# TicTacToe.net
KiCad netlist of a schematic drawn in EAGLE
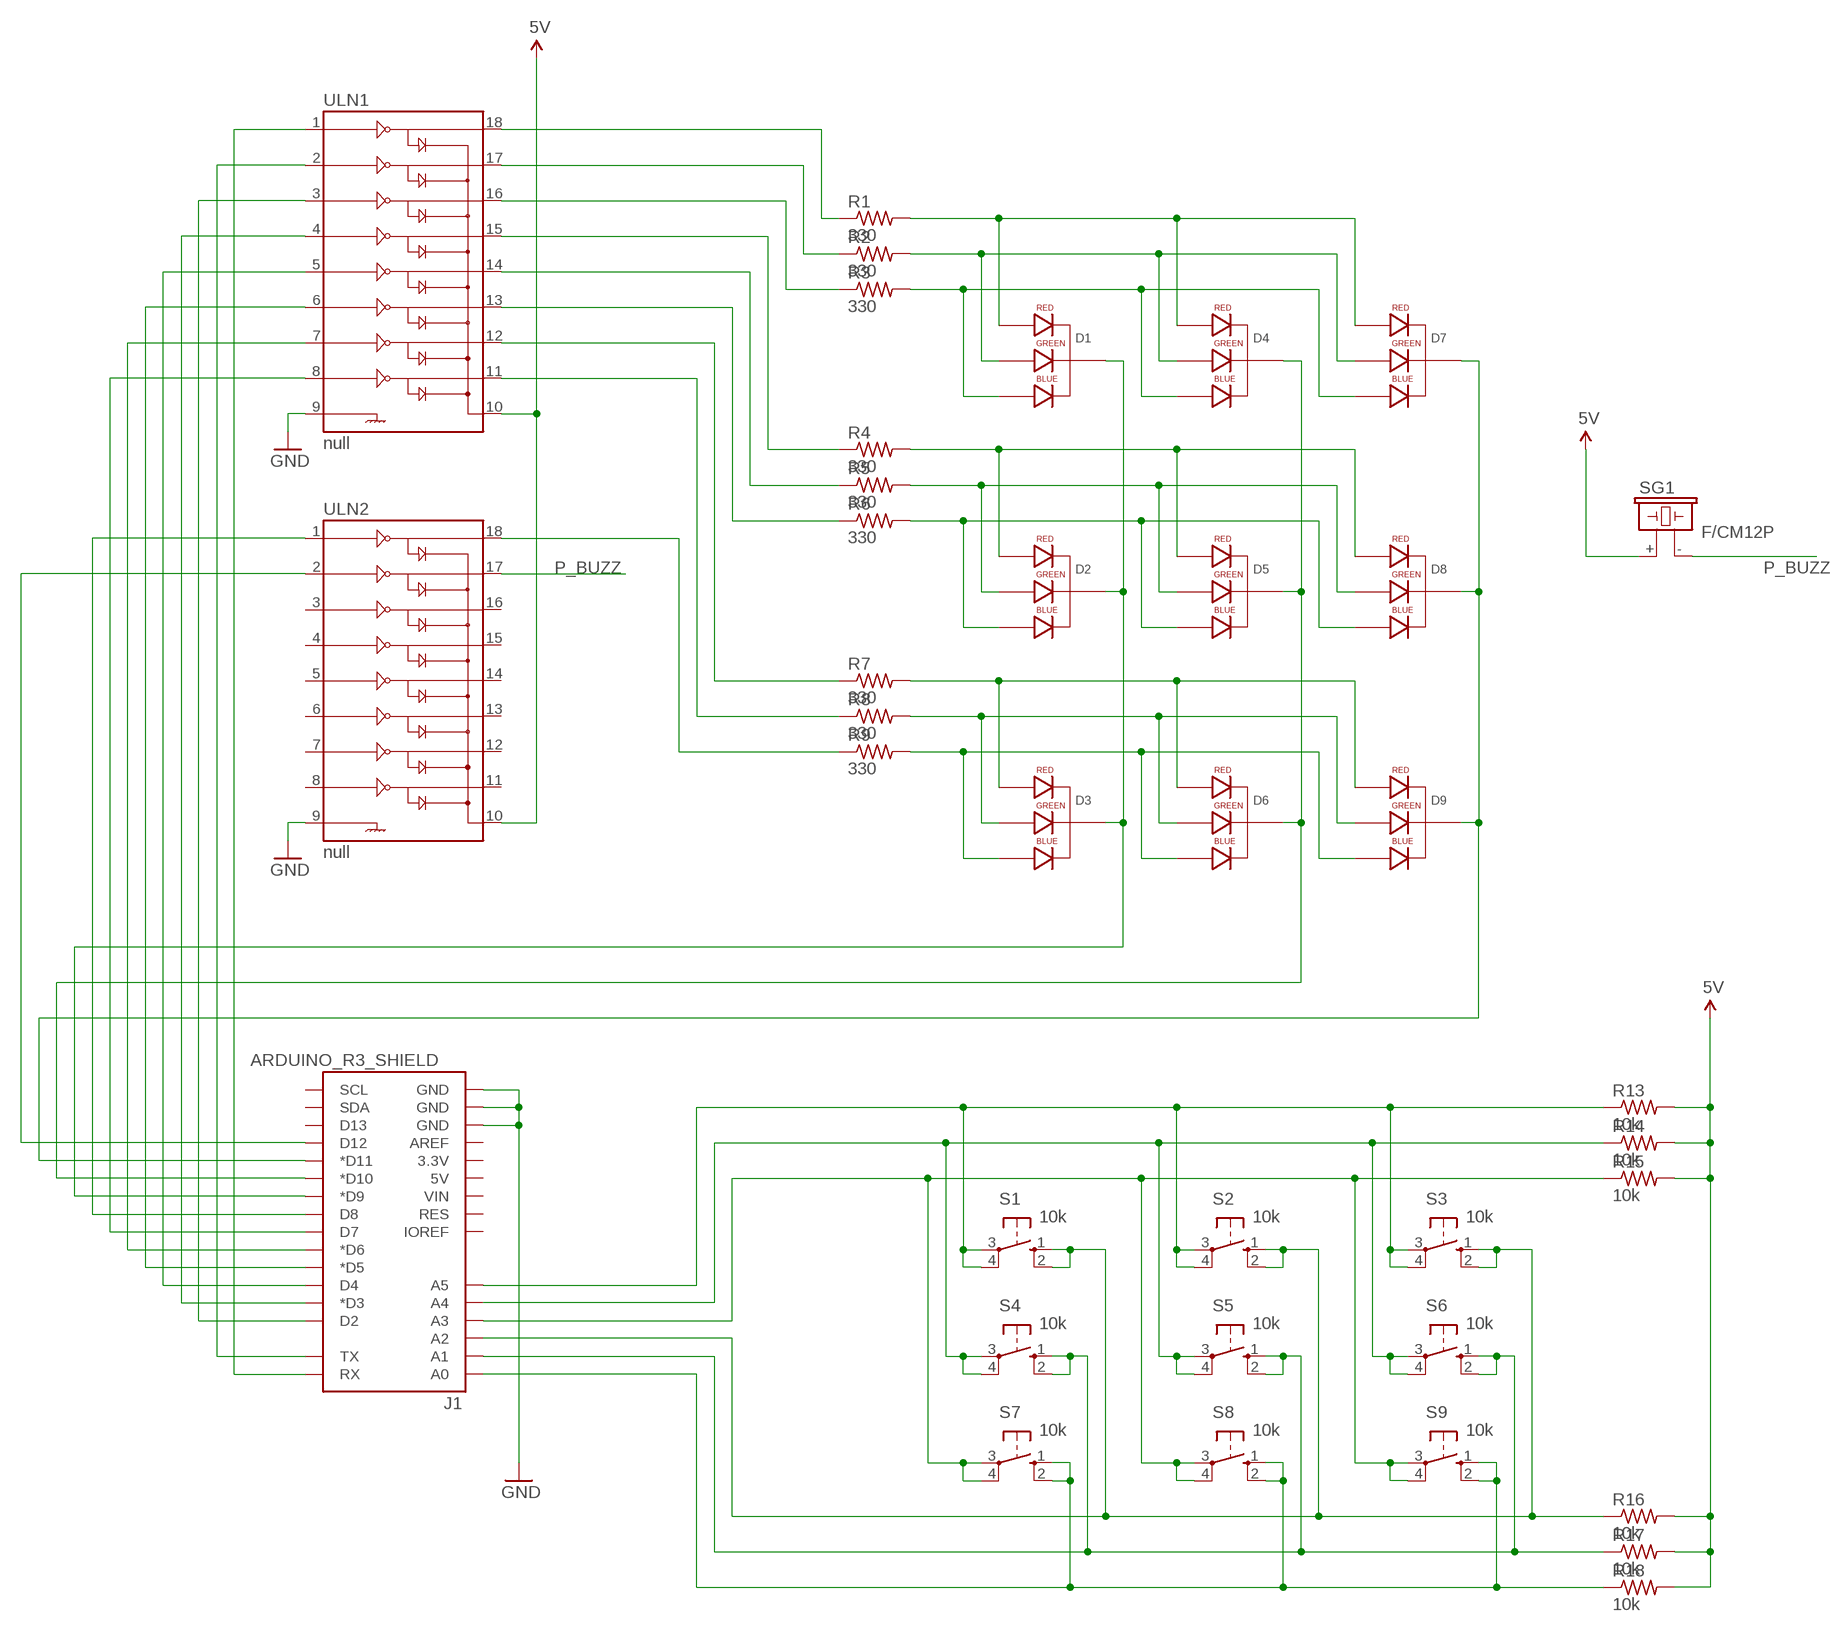
[diagram p0: schematic, sheet 1]

(export (version "E")
  (design (tool "Eeschema 10.0.6"))
  (components
    (comp (ref "D1")
      (value "LED-RGB-CC-THRUCLEAR")
      (footprint "eagle-import:LED-RGB-THRU")
      (libsource (lib "eagle-import") (part "LED-RGB-CC-THRUCLEAR"))
    )
    (comp (ref "D2")
      (value "LED-RGB-CC-THRUCLEAR")
      (footprint "eagle-import:LED-RGB-THRU")
      (libsource (lib "eagle-import") (part "LED-RGB-CC-THRUCLEAR"))
    )
    (comp (ref "D3")
      (value "LED-RGB-CC-THRUCLEAR")
      (footprint "eagle-import:LED-RGB-THRU")
      (libsource (lib "eagle-import") (part "LED-RGB-CC-THRUCLEAR"))
    )
    (comp (ref "D4")
      (value "LED-RGB-CC-THRUCLEAR")
      (footprint "eagle-import:LED-RGB-THRU")
      (libsource (lib "eagle-import") (part "LED-RGB-CC-THRUCLEAR"))
    )
    (comp (ref "D5")
      (value "LED-RGB-CC-THRUCLEAR")
      (footprint "eagle-import:LED-RGB-THRU")
      (libsource (lib "eagle-import") (part "LED-RGB-CC-THRUCLEAR"))
    )
    (comp (ref "D6")
      (value "LED-RGB-CC-THRUCLEAR")
      (footprint "eagle-import:LED-RGB-THRU")
      (libsource (lib "eagle-import") (part "LED-RGB-CC-THRUCLEAR"))
    )
    (comp (ref "D7")
      (value "LED-RGB-CC-THRUCLEAR")
      (footprint "eagle-import:LED-RGB-THRU")
      (libsource (lib "eagle-import") (part "LED-RGB-CC-THRUCLEAR"))
    )
    (comp (ref "D8")
      (value "LED-RGB-CC-THRUCLEAR")
      (footprint "eagle-import:LED-RGB-THRU")
      (libsource (lib "eagle-import") (part "LED-RGB-CC-THRUCLEAR"))
    )
    (comp (ref "D9")
      (value "LED-RGB-CC-THRUCLEAR")
      (footprint "eagle-import:LED-RGB-THRU")
      (libsource (lib "eagle-import") (part "LED-RGB-CC-THRUCLEAR"))
    )
    (comp (ref "J1")
      (value "ARDUINO_R3_SHIELD")
      (footprint "eagle-import:UNO_R3_SHIELD")
      (libsource (lib "eagle-import") (part "ARDUINO_R3_SHIELD"))
    )
    (comp (ref "R1")
      (value "330")
      (footprint "eagle-import:0204_7")
      (libsource (lib "eagle-import") (part "R-US_0204/7"))
    )
    (comp (ref "R2")
      (value "330")
      (footprint "eagle-import:0204_7")
      (libsource (lib "eagle-import") (part "R-US_0204/7"))
    )
    (comp (ref "R3")
      (value "330")
      (footprint "eagle-import:0204_7")
      (libsource (lib "eagle-import") (part "R-US_0204/7"))
    )
    (comp (ref "R4")
      (value "330")
      (footprint "eagle-import:0204_7")
      (libsource (lib "eagle-import") (part "R-US_0204/7"))
    )
    (comp (ref "R5")
      (value "330")
      (footprint "eagle-import:0204_7")
      (libsource (lib "eagle-import") (part "R-US_0204/7"))
    )
    (comp (ref "R6")
      (value "330")
      (footprint "eagle-import:0204_7")
      (libsource (lib "eagle-import") (part "R-US_0204/7"))
    )
    (comp (ref "R7")
      (value "330")
      (footprint "eagle-import:0204_7")
      (libsource (lib "eagle-import") (part "R-US_0204/7"))
    )
    (comp (ref "R8")
      (value "330")
      (footprint "eagle-import:0204_7")
      (libsource (lib "eagle-import") (part "R-US_0204/7"))
    )
    (comp (ref "R9")
      (value "330")
      (footprint "eagle-import:0204_7")
      (libsource (lib "eagle-import") (part "R-US_0204/7"))
    )
    (comp (ref "R13")
      (value "10k")
      (footprint "eagle-import:0204_7")
      (libsource (lib "eagle-import") (part "R-US_0204/7"))
    )
    (comp (ref "R14")
      (value "10k")
      (footprint "eagle-import:0204_7")
      (libsource (lib "eagle-import") (part "R-US_0204/7"))
    )
    (comp (ref "R15")
      (value "10k")
      (footprint "eagle-import:0204_7")
      (libsource (lib "eagle-import") (part "R-US_0204/7"))
    )
    (comp (ref "R16")
      (value "10k")
      (footprint "eagle-import:0204_7")
      (libsource (lib "eagle-import") (part "R-US_0204/7"))
    )
    (comp (ref "R17")
      (value "10k")
      (footprint "eagle-import:0204_7")
      (libsource (lib "eagle-import") (part "R-US_0204/7"))
    )
    (comp (ref "R18")
      (value "10k")
      (footprint "eagle-import:0204_7")
      (libsource (lib "eagle-import") (part "R-US_0204/7"))
    )
    (comp (ref "S1")
      (value "10k")
      (footprint "eagle-import:B3F-10XX")
      (fields (field (name "MPN") "B3F-1000"))
      (libsource (lib "eagle-import") (part "10-XX"))
    )
    (comp (ref "S2")
      (value "10k")
      (footprint "eagle-import:B3F-10XX")
      (fields (field (name "MPN") "B3F-1000"))
      (libsource (lib "eagle-import") (part "10-XX"))
    )
    (comp (ref "S3")
      (value "10k")
      (footprint "eagle-import:B3F-10XX")
      (fields (field (name "MPN") "B3F-1000"))
      (libsource (lib "eagle-import") (part "10-XX"))
    )
    (comp (ref "S4")
      (value "10k")
      (footprint "eagle-import:B3F-10XX")
      (fields (field (name "MPN") "B3F-1000"))
      (libsource (lib "eagle-import") (part "10-XX"))
    )
    (comp (ref "S5")
      (value "10k")
      (footprint "eagle-import:B3F-10XX")
      (fields (field (name "MPN") "B3F-1000"))
      (libsource (lib "eagle-import") (part "10-XX"))
    )
    (comp (ref "S6")
      (value "10k")
      (footprint "eagle-import:B3F-10XX")
      (fields (field (name "MPN") "B3F-1000"))
      (libsource (lib "eagle-import") (part "10-XX"))
    )
    (comp (ref "S7")
      (value "10k")
      (footprint "eagle-import:B3F-10XX")
      (fields (field (name "MPN") "B3F-1000"))
      (libsource (lib "eagle-import") (part "10-XX"))
    )
    (comp (ref "S8")
      (value "10k")
      (footprint "eagle-import:B3F-10XX")
      (fields (field (name "MPN") "B3F-1000"))
      (libsource (lib "eagle-import") (part "10-XX"))
    )
    (comp (ref "S9")
      (value "10k")
      (footprint "eagle-import:B3F-10XX")
      (fields (field (name "MPN") "B3F-1000"))
      (libsource (lib "eagle-import") (part "10-XX"))
    )
    (comp (ref "SG1")
      (value "F/CM12P")
      (footprint "eagle-import:F_CM12P")
      (libsource (lib "eagle-import") (part "F/CM12P"))
    )
    (comp (ref "ULN1")
      (value "null")
      (footprint "eagle-import:DIL18")
      (libsource (lib "eagle-import") (part "ULN2803DIP"))
    )
    (comp (ref "ULN2")
      (value "null")
      (footprint "eagle-import:DIL18")
      (libsource (lib "eagle-import") (part "ULN2803DIP"))
    )
  )
  (nets
    (net (code "1") (name "/P_BUZZ") (class "Default")
      (node (ref "SG1") (pin "-") (pinfunction "2_-") (pintype "passive"))
      (node (ref "ULN2") (pin "17") (pinfunction "17_17") (pintype "bidirectional"))
    )
    (net (code "2") (name "5V") (class "Default")
      (node (ref "R13") (pin "2") (pinfunction "2_2") (pintype "passive"))
      (node (ref "R14") (pin "2") (pinfunction "2_2") (pintype "passive"))
      (node (ref "R15") (pin "2") (pinfunction "2_2") (pintype "passive"))
      (node (ref "R16") (pin "2") (pinfunction "2_2") (pintype "passive"))
      (node (ref "R17") (pin "2") (pinfunction "2_2") (pintype "passive"))
      (node (ref "R18") (pin "2") (pinfunction "2_2") (pintype "passive"))
      (node (ref "SG1") (pin "+") (pinfunction "1_+") (pintype "passive"))
      (node (ref "ULN1") (pin "10") (pinfunction "10_10") (pintype "bidirectional"))
      (node (ref "ULN2") (pin "10") (pinfunction "10_10") (pintype "bidirectional"))
    )
    (net (code "3") (name "GND") (class "Default")
      (node (ref "J1") (pin "GND@0") (pinfunction "GND_GND@0") (pintype "bidirectional"))
      (node (ref "J1") (pin "GND@1") (pinfunction "GND_GND@1") (pintype "bidirectional"))
      (node (ref "J1") (pin "GND@2") (pinfunction "GND_GND@2") (pintype "bidirectional"))
      (node (ref "ULN1") (pin "9") (pinfunction "9_9") (pintype "bidirectional"))
      (node (ref "ULN2") (pin "9") (pinfunction "9_9") (pintype "bidirectional"))
    )
    (net (code "4") (name "Net-(D1-BLUE_CATHODE)") (class "Default")
      (node (ref "D1") (pin "4") (pinfunction "BLUE_CATHODE_4") (pintype "bidirectional"))
      (node (ref "D4") (pin "4") (pinfunction "BLUE_CATHODE_4") (pintype "bidirectional"))
      (node (ref "D7") (pin "4") (pinfunction "BLUE_CATHODE_4") (pintype "bidirectional"))
      (node (ref "R3") (pin "2") (pinfunction "2_2") (pintype "passive"))
    )
    (net (code "5") (name "Net-(D1-CATHODE)") (class "Default")
      (node (ref "D1") (pin "2") (pinfunction "CATHODE_2") (pintype "bidirectional"))
      (node (ref "D2") (pin "2") (pinfunction "CATHODE_2") (pintype "bidirectional"))
      (node (ref "D3") (pin "2") (pinfunction "CATHODE_2") (pintype "bidirectional"))
      (node (ref "J1") (pin "D9") (pinfunction "*D9_D9") (pintype "bidirectional"))
    )
    (net (code "6") (name "Net-(D1-GREEN_CATHODE)") (class "Default")
      (node (ref "D1") (pin "3") (pinfunction "GREEN_CATHODE_3") (pintype "bidirectional"))
      (node (ref "D4") (pin "3") (pinfunction "GREEN_CATHODE_3") (pintype "bidirectional"))
      (node (ref "D7") (pin "3") (pinfunction "GREEN_CATHODE_3") (pintype "bidirectional"))
      (node (ref "R2") (pin "2") (pinfunction "2_2") (pintype "passive"))
    )
    (net (code "7") (name "Net-(D1-RED_CATHODE)") (class "Default")
      (node (ref "D1") (pin "1") (pinfunction "RED_CATHODE_1") (pintype "bidirectional"))
      (node (ref "D4") (pin "1") (pinfunction "RED_CATHODE_1") (pintype "bidirectional"))
      (node (ref "D7") (pin "1") (pinfunction "RED_CATHODE_1") (pintype "bidirectional"))
      (node (ref "R1") (pin "2") (pinfunction "2_2") (pintype "passive"))
    )
    (net (code "8") (name "Net-(D2-BLUE_CATHODE)") (class "Default")
      (node (ref "D2") (pin "4") (pinfunction "BLUE_CATHODE_4") (pintype "bidirectional"))
      (node (ref "D5") (pin "4") (pinfunction "BLUE_CATHODE_4") (pintype "bidirectional"))
      (node (ref "D8") (pin "4") (pinfunction "BLUE_CATHODE_4") (pintype "bidirectional"))
      (node (ref "R6") (pin "2") (pinfunction "2_2") (pintype "passive"))
    )
    (net (code "9") (name "Net-(D2-GREEN_CATHODE)") (class "Default")
      (node (ref "D2") (pin "3") (pinfunction "GREEN_CATHODE_3") (pintype "bidirectional"))
      (node (ref "D5") (pin "3") (pinfunction "GREEN_CATHODE_3") (pintype "bidirectional"))
      (node (ref "D8") (pin "3") (pinfunction "GREEN_CATHODE_3") (pintype "bidirectional"))
      (node (ref "R5") (pin "2") (pinfunction "2_2") (pintype "passive"))
    )
    (net (code "10") (name "Net-(D2-RED_CATHODE)") (class "Default")
      (node (ref "D2") (pin "1") (pinfunction "RED_CATHODE_1") (pintype "bidirectional"))
      (node (ref "D5") (pin "1") (pinfunction "RED_CATHODE_1") (pintype "bidirectional"))
      (node (ref "D8") (pin "1") (pinfunction "RED_CATHODE_1") (pintype "bidirectional"))
      (node (ref "R4") (pin "2") (pinfunction "2_2") (pintype "passive"))
    )
    (net (code "11") (name "Net-(D3-BLUE_CATHODE)") (class "Default")
      (node (ref "D3") (pin "4") (pinfunction "BLUE_CATHODE_4") (pintype "bidirectional"))
      (node (ref "D6") (pin "4") (pinfunction "BLUE_CATHODE_4") (pintype "bidirectional"))
      (node (ref "D9") (pin "4") (pinfunction "BLUE_CATHODE_4") (pintype "bidirectional"))
      (node (ref "R9") (pin "2") (pinfunction "2_2") (pintype "passive"))
    )
    (net (code "12") (name "Net-(D3-GREEN_CATHODE)") (class "Default")
      (node (ref "D3") (pin "3") (pinfunction "GREEN_CATHODE_3") (pintype "bidirectional"))
      (node (ref "D6") (pin "3") (pinfunction "GREEN_CATHODE_3") (pintype "bidirectional"))
      (node (ref "D9") (pin "3") (pinfunction "GREEN_CATHODE_3") (pintype "bidirectional"))
      (node (ref "R8") (pin "2") (pinfunction "2_2") (pintype "passive"))
    )
    (net (code "13") (name "Net-(D3-RED_CATHODE)") (class "Default")
      (node (ref "D3") (pin "1") (pinfunction "RED_CATHODE_1") (pintype "bidirectional"))
      (node (ref "D6") (pin "1") (pinfunction "RED_CATHODE_1") (pintype "bidirectional"))
      (node (ref "D9") (pin "1") (pinfunction "RED_CATHODE_1") (pintype "bidirectional"))
      (node (ref "R7") (pin "2") (pinfunction "2_2") (pintype "passive"))
    )
    (net (code "14") (name "Net-(D4-CATHODE)") (class "Default")
      (node (ref "D4") (pin "2") (pinfunction "CATHODE_2") (pintype "bidirectional"))
      (node (ref "D5") (pin "2") (pinfunction "CATHODE_2") (pintype "bidirectional"))
      (node (ref "D6") (pin "2") (pinfunction "CATHODE_2") (pintype "bidirectional"))
      (node (ref "J1") (pin "D10") (pinfunction "*D10_D10") (pintype "bidirectional"))
    )
    (net (code "15") (name "Net-(D7-CATHODE)") (class "Default")
      (node (ref "D7") (pin "2") (pinfunction "CATHODE_2") (pintype "bidirectional"))
      (node (ref "D8") (pin "2") (pinfunction "CATHODE_2") (pintype "bidirectional"))
      (node (ref "D9") (pin "2") (pinfunction "CATHODE_2") (pintype "bidirectional"))
      (node (ref "J1") (pin "D11") (pinfunction "*D11_D11") (pintype "bidirectional"))
    )
    (net (code "16") (name "Net-(J1-*D3)") (class "Default")
      (node (ref "J1") (pin "D3") (pinfunction "*D3_D3") (pintype "bidirectional"))
      (node (ref "ULN1") (pin "4") (pinfunction "4_4") (pintype "bidirectional"))
    )
    (net (code "17") (name "Net-(J1-*D5)") (class "Default")
      (node (ref "J1") (pin "D5") (pinfunction "*D5_D5") (pintype "bidirectional"))
      (node (ref "ULN1") (pin "6") (pinfunction "6_6") (pintype "bidirectional"))
    )
    (net (code "18") (name "Net-(J1-*D6)") (class "Default")
      (node (ref "J1") (pin "D6") (pinfunction "*D6_D6") (pintype "bidirectional"))
      (node (ref "ULN1") (pin "7") (pinfunction "7_7") (pintype "bidirectional"))
    )
    (net (code "19") (name "Net-(J1-PadD2)") (class "Default")
      (node (ref "J1") (pin "D2") (pinfunction "D2_D2") (pintype "bidirectional"))
      (node (ref "ULN1") (pin "3") (pinfunction "3_3") (pintype "bidirectional"))
    )
    (net (code "20") (name "Net-(J1-PadD4)") (class "Default")
      (node (ref "J1") (pin "D4") (pinfunction "D4_D4") (pintype "bidirectional"))
      (node (ref "ULN1") (pin "5") (pinfunction "5_5") (pintype "bidirectional"))
    )
    (net (code "21") (name "Net-(J1-PadD7)") (class "Default")
      (node (ref "J1") (pin "D7") (pinfunction "D7_D7") (pintype "bidirectional"))
      (node (ref "ULN1") (pin "8") (pinfunction "8_8") (pintype "bidirectional"))
    )
    (net (code "22") (name "Net-(J1-PadD8)") (class "Default")
      (node (ref "J1") (pin "D8") (pinfunction "D8_D8") (pintype "bidirectional"))
      (node (ref "ULN2") (pin "1") (pinfunction "1_1") (pintype "bidirectional"))
    )
    (net (code "23") (name "Net-(J1-PadD12)") (class "Default")
      (node (ref "J1") (pin "D12") (pinfunction "D12_D12") (pintype "bidirectional"))
      (node (ref "ULN2") (pin "2") (pinfunction "2_2") (pintype "bidirectional"))
    )
    (net (code "24") (name "Net-(J1-PadRX)") (class "Default")
      (node (ref "J1") (pin "RX") (pinfunction "RX_RX") (pintype "bidirectional"))
      (node (ref "ULN1") (pin "1") (pinfunction "1_1") (pintype "bidirectional"))
    )
    (net (code "25") (name "Net-(J1-PadTX)") (class "Default")
      (node (ref "J1") (pin "TX") (pinfunction "TX_TX") (pintype "bidirectional"))
      (node (ref "ULN1") (pin "2") (pinfunction "2_2") (pintype "bidirectional"))
    )
    (net (code "26") (name "Net-(R1-Pad1)") (class "Default")
      (node (ref "R1") (pin "1") (pinfunction "1_1") (pintype "passive"))
      (node (ref "ULN1") (pin "18") (pinfunction "18_18") (pintype "bidirectional"))
    )
    (net (code "27") (name "Net-(R2-Pad1)") (class "Default")
      (node (ref "R2") (pin "1") (pinfunction "1_1") (pintype "passive"))
      (node (ref "ULN1") (pin "17") (pinfunction "17_17") (pintype "bidirectional"))
    )
    (net (code "28") (name "Net-(R3-Pad1)") (class "Default")
      (node (ref "R3") (pin "1") (pinfunction "1_1") (pintype "passive"))
      (node (ref "ULN1") (pin "16") (pinfunction "16_16") (pintype "bidirectional"))
    )
    (net (code "29") (name "Net-(R4-Pad1)") (class "Default")
      (node (ref "R4") (pin "1") (pinfunction "1_1") (pintype "passive"))
      (node (ref "ULN1") (pin "15") (pinfunction "15_15") (pintype "bidirectional"))
    )
    (net (code "30") (name "Net-(R5-Pad1)") (class "Default")
      (node (ref "R5") (pin "1") (pinfunction "1_1") (pintype "passive"))
      (node (ref "ULN1") (pin "14") (pinfunction "14_14") (pintype "bidirectional"))
    )
    (net (code "31") (name "Net-(R6-Pad1)") (class "Default")
      (node (ref "R6") (pin "1") (pinfunction "1_1") (pintype "passive"))
      (node (ref "ULN1") (pin "13") (pinfunction "13_13") (pintype "bidirectional"))
    )
    (net (code "32") (name "Net-(R7-Pad1)") (class "Default")
      (node (ref "R7") (pin "1") (pinfunction "1_1") (pintype "passive"))
      (node (ref "ULN1") (pin "12") (pinfunction "12_12") (pintype "bidirectional"))
    )
    (net (code "33") (name "Net-(R8-Pad1)") (class "Default")
      (node (ref "R8") (pin "1") (pinfunction "1_1") (pintype "passive"))
      (node (ref "ULN1") (pin "11") (pinfunction "11_11") (pintype "bidirectional"))
    )
    (net (code "34") (name "Net-(R9-Pad1)") (class "Default")
      (node (ref "R9") (pin "1") (pinfunction "1_1") (pintype "passive"))
      (node (ref "ULN2") (pin "18") (pinfunction "18_18") (pintype "bidirectional"))
    )
    (net (code "35") (name "Net-(S1-P)") (class "Default")
      (node (ref "J1") (pin "A5") (pinfunction "A5_A5") (pintype "bidirectional"))
      (node (ref "R13") (pin "1") (pinfunction "1_1") (pintype "passive"))
      (node (ref "S1") (pin "3") (pinfunction "P_3") (pintype "passive"))
      (node (ref "S1") (pin "4") (pinfunction "P1_4") (pintype "passive"))
      (node (ref "S2") (pin "3") (pinfunction "P_3") (pintype "passive"))
      (node (ref "S2") (pin "4") (pinfunction "P1_4") (pintype "passive"))
      (node (ref "S3") (pin "3") (pinfunction "P_3") (pintype "passive"))
      (node (ref "S3") (pin "4") (pinfunction "P1_4") (pintype "passive"))
    )
    (net (code "36") (name "Net-(S1-S)") (class "Default")
      (node (ref "J1") (pin "A2") (pinfunction "A2_A2") (pintype "bidirectional"))
      (node (ref "R16") (pin "1") (pinfunction "1_1") (pintype "passive"))
      (node (ref "S1") (pin "1") (pinfunction "S_1") (pintype "passive"))
      (node (ref "S1") (pin "2") (pinfunction "S1_2") (pintype "passive"))
      (node (ref "S2") (pin "1") (pinfunction "S_1") (pintype "passive"))
      (node (ref "S2") (pin "2") (pinfunction "S1_2") (pintype "passive"))
      (node (ref "S3") (pin "1") (pinfunction "S_1") (pintype "passive"))
      (node (ref "S3") (pin "2") (pinfunction "S1_2") (pintype "passive"))
    )
    (net (code "37") (name "Net-(S4-P)") (class "Default")
      (node (ref "J1") (pin "A4") (pinfunction "A4_A4") (pintype "bidirectional"))
      (node (ref "R14") (pin "1") (pinfunction "1_1") (pintype "passive"))
      (node (ref "S4") (pin "3") (pinfunction "P_3") (pintype "passive"))
      (node (ref "S4") (pin "4") (pinfunction "P1_4") (pintype "passive"))
      (node (ref "S5") (pin "3") (pinfunction "P_3") (pintype "passive"))
      (node (ref "S5") (pin "4") (pinfunction "P1_4") (pintype "passive"))
      (node (ref "S6") (pin "3") (pinfunction "P_3") (pintype "passive"))
      (node (ref "S6") (pin "4") (pinfunction "P1_4") (pintype "passive"))
    )
    (net (code "38") (name "Net-(S4-S)") (class "Default")
      (node (ref "J1") (pin "A1") (pinfunction "A1_A1") (pintype "bidirectional"))
      (node (ref "R17") (pin "1") (pinfunction "1_1") (pintype "passive"))
      (node (ref "S4") (pin "1") (pinfunction "S_1") (pintype "passive"))
      (node (ref "S4") (pin "2") (pinfunction "S1_2") (pintype "passive"))
      (node (ref "S5") (pin "1") (pinfunction "S_1") (pintype "passive"))
      (node (ref "S5") (pin "2") (pinfunction "S1_2") (pintype "passive"))
      (node (ref "S6") (pin "1") (pinfunction "S_1") (pintype "passive"))
      (node (ref "S6") (pin "2") (pinfunction "S1_2") (pintype "passive"))
    )
    (net (code "39") (name "Net-(S7-P)") (class "Default")
      (node (ref "J1") (pin "A3") (pinfunction "A3_A3") (pintype "bidirectional"))
      (node (ref "R15") (pin "1") (pinfunction "1_1") (pintype "passive"))
      (node (ref "S7") (pin "3") (pinfunction "P_3") (pintype "passive"))
      (node (ref "S7") (pin "4") (pinfunction "P1_4") (pintype "passive"))
      (node (ref "S8") (pin "3") (pinfunction "P_3") (pintype "passive"))
      (node (ref "S8") (pin "4") (pinfunction "P1_4") (pintype "passive"))
      (node (ref "S9") (pin "3") (pinfunction "P_3") (pintype "passive"))
      (node (ref "S9") (pin "4") (pinfunction "P1_4") (pintype "passive"))
    )
    (net (code "40") (name "Net-(S7-S)") (class "Default")
      (node (ref "J1") (pin "A0") (pinfunction "A0_A0") (pintype "bidirectional"))
      (node (ref "R18") (pin "1") (pinfunction "1_1") (pintype "passive"))
      (node (ref "S7") (pin "1") (pinfunction "S_1") (pintype "passive"))
      (node (ref "S7") (pin "2") (pinfunction "S1_2") (pintype "passive"))
      (node (ref "S8") (pin "1") (pinfunction "S_1") (pintype "passive"))
      (node (ref "S8") (pin "2") (pinfunction "S1_2") (pintype "passive"))
      (node (ref "S9") (pin "1") (pinfunction "S_1") (pintype "passive"))
      (node (ref "S9") (pin "2") (pinfunction "S1_2") (pintype "passive"))
    )
    (net (code "41") (name "unconnected-(J1-Pad3.3V)") (class "Default")
      (node (ref "J1") (pin "3.3V") (pinfunction "3.3V_3.3V") (pintype "bidirectional"))
    )
    (net (code "42") (name "unconnected-(J1-Pad5V)") (class "Default")
      (node (ref "J1") (pin "5V") (pinfunction "5V_5V") (pintype "bidirectional"))
    )
    (net (code "43") (name "unconnected-(J1-PadAREF)") (class "Default")
      (node (ref "J1") (pin "AREF") (pinfunction "AREF_AREF") (pintype "bidirectional"))
    )
    (net (code "44") (name "unconnected-(J1-PadD13)") (class "Default")
      (node (ref "J1") (pin "D13") (pinfunction "D13_D13") (pintype "bidirectional"))
    )
    (net (code "45") (name "unconnected-(J1-PadIOREF)") (class "Default")
      (node (ref "J1") (pin "IOREF") (pinfunction "IOREF_IOREF") (pintype "bidirectional"))
    )
    (net (code "46") (name "unconnected-(J1-PadRES)") (class "Default")
      (node (ref "J1") (pin "RES") (pinfunction "RES_RES") (pintype "bidirectional"))
    )
    (net (code "47") (name "unconnected-(J1-PadSCL)") (class "Default")
      (node (ref "J1") (pin "SCL") (pinfunction "SCL_SCL") (pintype "bidirectional"))
    )
    (net (code "48") (name "unconnected-(J1-PadSDA)") (class "Default")
      (node (ref "J1") (pin "SDA") (pinfunction "SDA_SDA") (pintype "bidirectional"))
    )
    (net (code "49") (name "unconnected-(J1-PadVIN)") (class "Default")
      (node (ref "J1") (pin "VIN") (pinfunction "VIN_VIN") (pintype "bidirectional"))
    )
    (net (code "50") (name "unconnected-(ULN2-Pad3)") (class "Default")
      (node (ref "ULN2") (pin "3") (pinfunction "3_3") (pintype "bidirectional"))
    )
    (net (code "51") (name "unconnected-(ULN2-Pad4)") (class "Default")
      (node (ref "ULN2") (pin "4") (pinfunction "4_4") (pintype "bidirectional"))
    )
    (net (code "52") (name "unconnected-(ULN2-Pad5)") (class "Default")
      (node (ref "ULN2") (pin "5") (pinfunction "5_5") (pintype "bidirectional"))
    )
    (net (code "53") (name "unconnected-(ULN2-Pad6)") (class "Default")
      (node (ref "ULN2") (pin "6") (pinfunction "6_6") (pintype "bidirectional"))
    )
    (net (code "54") (name "unconnected-(ULN2-Pad7)") (class "Default")
      (node (ref "ULN2") (pin "7") (pinfunction "7_7") (pintype "bidirectional"))
    )
    (net (code "55") (name "unconnected-(ULN2-Pad8)") (class "Default")
      (node (ref "ULN2") (pin "8") (pinfunction "8_8") (pintype "bidirectional"))
    )
    (net (code "56") (name "unconnected-(ULN2-Pad11)") (class "Default")
      (node (ref "ULN2") (pin "11") (pinfunction "11_11") (pintype "bidirectional"))
    )
    (net (code "57") (name "unconnected-(ULN2-Pad12)") (class "Default")
      (node (ref "ULN2") (pin "12") (pinfunction "12_12") (pintype "bidirectional"))
    )
    (net (code "58") (name "unconnected-(ULN2-Pad13)") (class "Default")
      (node (ref "ULN2") (pin "13") (pinfunction "13_13") (pintype "bidirectional"))
    )
    (net (code "59") (name "unconnected-(ULN2-Pad14)") (class "Default")
      (node (ref "ULN2") (pin "14") (pinfunction "14_14") (pintype "bidirectional"))
    )
    (net (code "60") (name "unconnected-(ULN2-Pad15)") (class "Default")
      (node (ref "ULN2") (pin "15") (pinfunction "15_15") (pintype "bidirectional"))
    )
    (net (code "61") (name "unconnected-(ULN2-Pad16)") (class "Default")
      (node (ref "ULN2") (pin "16") (pinfunction "16_16") (pintype "bidirectional"))
    )
  )
)
